# design.net
KiCad netlist of a schematic drawn in EasyEDA Pro
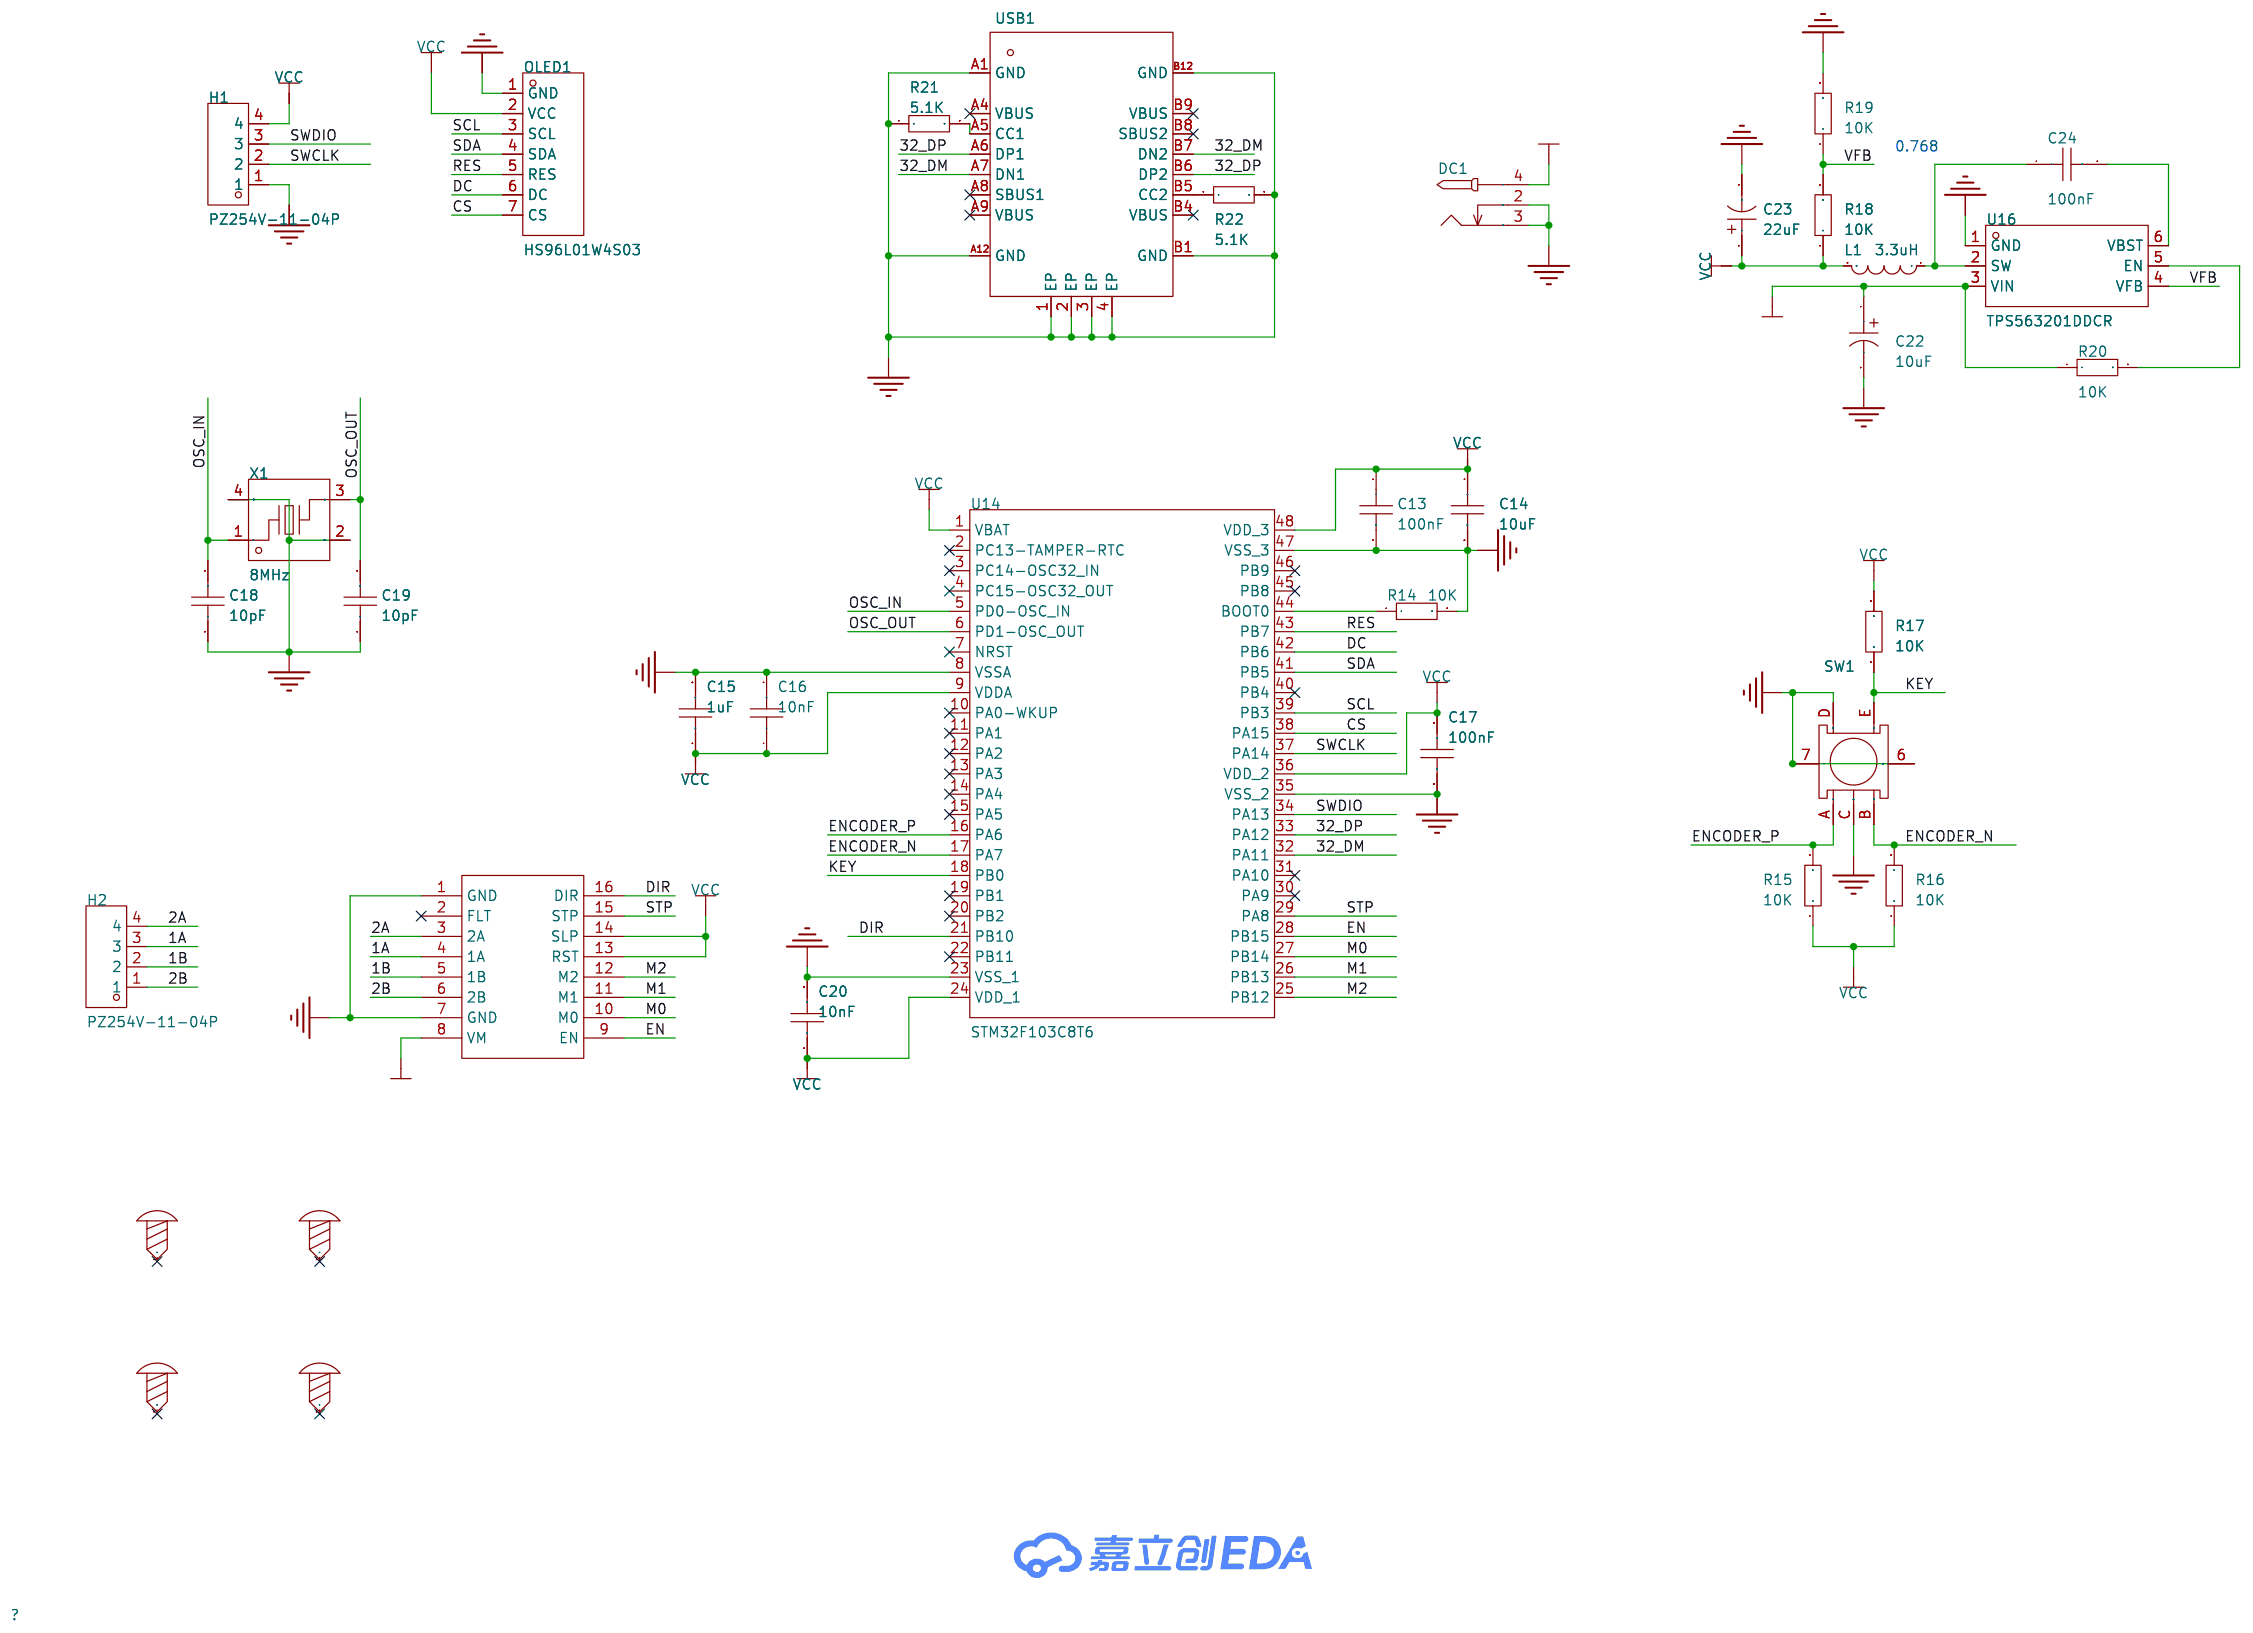
[diagram p0: schematic sheet]

(export (version "E")
  (design (tool "Eeschema 10.0.6"))
  (components
    (comp (ref "C13")
      (value "100nF")
      (footprint "easyedapro:C0603")
      (libsource (lib "easyedapro") (part "Capacitance"))
    )
    (comp (ref "C14")
      (value "10uF")
      (footprint "easyedapro:C0603")
      (libsource (lib "easyedapro") (part "Capacitance"))
    )
    (comp (ref "C15")
      (value "1uF")
      (footprint "easyedapro:C0603")
      (libsource (lib "easyedapro") (part "Capacitance"))
    )
    (comp (ref "C16")
      (value "10nF")
      (footprint "easyedapro:C0603")
      (libsource (lib "easyedapro") (part "Capacitance"))
    )
    (comp (ref "C17")
      (value "100nF")
      (footprint "easyedapro:C0603")
      (libsource (lib "easyedapro") (part "Capacitance"))
    )
    (comp (ref "C18")
      (value "10pF")
      (footprint "easyedapro:C0603")
      (libsource (lib "easyedapro") (part "Capacitance"))
    )
    (comp (ref "C19")
      (value "10pF")
      (footprint "easyedapro:C0603")
      (libsource (lib "easyedapro") (part "Capacitance"))
    )
    (comp (ref "C20")
      (value "10nF")
      (footprint "easyedapro:C0603")
      (libsource (lib "easyedapro") (part "Capacitance"))
    )
    (comp (ref "C22")
      (value "10uF")
      (footprint "easyedapro:CAP-TH_BD4.0-P1.50-D0.5-FD")
      (description "容值:10uF;精度:±20%;额定电压:16V;纹波电流:28mA@120Hz;等效串联电阻(ESR):-;")
      (fields
        (field (name "Manufacturer Part") "ECE-A1CKS100I")
        (field (name "Manufacturer") "PANASONIC(松下)")
      )
      (libsource (lib "easyedapro") (part "ECE-A1CKS100I"))
    )
    (comp (ref "C23")
      (value "22uF")
      (footprint "easyedapro:CAP-TH_BD5.0-P2.00-D0.5-FD-1")
      (description "容值:22uF;精度:±20%;额定电压:50V;")
      (fields (field (name "Manufacturer Part") "RGA220M1HBK-0511") (field (name "Manufacturer") "Lelon(立隆)"))
      (libsource (lib "easyedapro") (part "RGA220M1HBK-0511"))
    )
    (comp (ref "C24")
      (value "100nF")
      (footprint "easyedapro:C0603")
      (libsource (lib "easyedapro") (part "Capacitance"))
    )
    (comp (ref "DC1")
      (value "~")
      (footprint "easyedapro:DC-2.0")
      (libsource (lib "easyedapro") (part "DC电源接口"))
    )
    (comp (ref "H1")
      (value "PZ254V-11-04P")
      (footprint "easyedapro:HDR-TH_4P-P2.54-V-F")
      (fields (field (name "Manufacturer") "XFCN(兴飞)"))
      (libsource (lib "easyedapro") (part "2.54-1*4P母"))
    )
    (comp (ref "H2")
      (value "PZ254V-11-04P")
      (footprint "easyedapro:HDR-TH_4P-P2.54-V-F")
      (fields (field (name "Manufacturer") "XFCN(兴飞)"))
      (libsource (lib "easyedapro") (part "2.54-1*4P母"))
    )
    (comp (ref "L1")
      (value "3.3uH")
      (footprint "easyedapro:IND-SMD_L2.5-W2.0_AHP252010X")
      (description "电感值:3.3uH;精度:±20%;饱和电流(Isat):1.25A;")
      (fields (field (name "Manufacturer Part") "74404024033") (field (name "Manufacturer") "Wurth(伍尔特)"))
      (libsource (lib "easyedapro") (part "74404024033"))
    )
    (comp (ref "OLED1")
      (value "HS96L01W4S03")
      (footprint "easyedapro:OLED-TH_HS96L01W4S03")
      (fields (field (name "Manufacturer") "HS(汉昇)"))
      (libsource (lib "easyedapro") (part "HS96L01W4S03"))
    )
    (comp (ref "R14") (value "10K") (footprint "easyedapro:R0603") (libsource (lib "easyedapro") (part "电阻")))
    (comp (ref "R15") (value "10K") (footprint "easyedapro:R0603") (libsource (lib "easyedapro") (part "电阻")))
    (comp (ref "R16") (value "10K") (footprint "easyedapro:R0603") (libsource (lib "easyedapro") (part "电阻")))
    (comp (ref "R17") (value "10K") (footprint "easyedapro:R0603") (libsource (lib "easyedapro") (part "电阻")))
    (comp (ref "R18") (value "10K") (footprint "easyedapro:R0603") (libsource (lib "easyedapro") (part "电阻")))
    (comp (ref "R19") (value "10K") (footprint "easyedapro:R0603") (libsource (lib "easyedapro") (part "电阻")))
    (comp (ref "R20") (value "10K") (footprint "easyedapro:R0603") (libsource (lib "easyedapro") (part "电阻")))
    (comp (ref "R21")
      (value "5.1K")
      (footprint "easyedapro:R0603")
      (libsource (lib "easyedapro") (part "电阻"))
    )
    (comp (ref "R22")
      (value "5.1K")
      (footprint "easyedapro:R0603")
      (libsource (lib "easyedapro") (part "电阻"))
    )
    (comp (ref "SCREW1")
      (value "~")
      (footprint "easyedapro:M3螺丝")
      (libsource (lib "easyedapro") (part "螺丝孔"))
    )
    (comp (ref "SCREW2")
      (value "~")
      (footprint "easyedapro:M3螺丝")
      (libsource (lib "easyedapro") (part "螺丝孔"))
    )
    (comp (ref "SCREW3")
      (value "~")
      (footprint "easyedapro:M3螺丝")
      (libsource (lib "easyedapro") (part "螺丝孔"))
    )
    (comp (ref "SCREW4")
      (value "~")
      (footprint "easyedapro:M3螺丝")
      (libsource (lib "easyedapro") (part "螺丝孔"))
    )
    (comp (ref "SW1")
      (value "~")
      (footprint "easyedapro:旋转编码器")
      (libsource (lib "easyedapro") (part "旋转编码器"))
    )
    (comp (ref "U1")
      (value "~")
      (footprint "easyedapro:DRV8825模块")
      (libsource (lib "easyedapro") (part "DRV8825模块"))
    )
    (comp (ref "U14")
      (value "STM32F103C8T6")
      (footprint "easyedapro:LQFP-48_L7.0-W7.0-P0.50-LS9.0-BL")
      (fields (field (name "Manufacturer") "ST(意法半导体)"))
      (libsource (lib "easyedapro") (part "STM32F103C8T6"))
    )
    (comp (ref "U16")
      (value "TPS563201DDCR")
      (footprint "easyedapro:SOT-23-6_L2.9-W1.6-P0.95-LS2.8-BR")
      (description "功能类型:降压型;输出类型:可调;工作电压:4.5V~17V;输出电压:768mV~7V;输出电流:3A;")
      (fields (field (name "Manufacturer") "TI(德州仪器)"))
      (libsource (lib "easyedapro") (part "TPS563201DDCR"))
    )
    (comp (ref "USB1")
      (value "~")
      (footprint "easyedapro:USB_TYPE-C-16P")
      (libsource (lib "easyedapro") (part "USB_TYPE-C-16P"))
    )
    (comp (ref "X1")
      (value "8MHz")
      (footprint "easyedapro:CRYSTAL-SMD_4P-L3.2-W2.5-BL")
      (description "晶振类型:贴片晶振;频率:8MHz;常温频差:±10ppm;负载电容:20pF;频率稳定度:±20ppm;")
      (fields (field (name "Manufacturer Part") "X32258MSB4SI") (field (name "Manufacturer") "YXC(扬兴晶振)"))
      (libsource (lib "easyedapro") (part "X32258MSB4SI"))
    )
  )
  (nets
    (net (code "1") (name "/1A") (class "Default")
      (node (ref "H2") (pin "3") (pinfunction "3_3") (pintype "unspecified"))
      (node (ref "U1") (pin "4") (pinfunction "1A_4") (pintype "input"))
    )
    (net (code "2") (name "/1B") (class "Default")
      (node (ref "H2") (pin "2") (pinfunction "2_2") (pintype "unspecified"))
      (node (ref "U1") (pin "5") (pinfunction "1B_5") (pintype "input"))
    )
    (net (code "3") (name "/2A") (class "Default")
      (node (ref "H2") (pin "4") (pinfunction "4_4") (pintype "unspecified"))
      (node (ref "U1") (pin "3") (pinfunction "2A_3") (pintype "input"))
    )
    (net (code "4") (name "/2B") (class "Default")
      (node (ref "H2") (pin "1") (pinfunction "1_1") (pintype "unspecified"))
      (node (ref "U1") (pin "6") (pinfunction "2B_6") (pintype "input"))
    )
    (net (code "5") (name "/32_DM") (class "Default")
      (node (ref "U14") (pin "32") (pinfunction "PA11_32") (pintype "unspecified"))
      (node (ref "USB1") (pin "A7") (pinfunction "DN1_A7") (pintype "input"))
      (node (ref "USB1") (pin "B7") (pinfunction "DN2_B7") (pintype "input"))
    )
    (net (code "6") (name "/32_DP") (class "Default")
      (node (ref "U14") (pin "33") (pinfunction "PA12_33") (pintype "unspecified"))
      (node (ref "USB1") (pin "A6") (pinfunction "DP1_A6") (pintype "input"))
      (node (ref "USB1") (pin "B6") (pinfunction "DP2_B6") (pintype "input"))
    )
    (net (code "7") (name "/CS") (class "Default")
      (node (ref "OLED1") (pin "7") (pinfunction "CS_7") (pintype "unspecified"))
      (node (ref "U14") (pin "38") (pinfunction "PA15_38") (pintype "unspecified"))
    )
    (net (code "8") (name "/DC") (class "Default")
      (node (ref "OLED1") (pin "6") (pinfunction "DC_6") (pintype "unspecified"))
      (node (ref "U14") (pin "42") (pinfunction "PB6_42") (pintype "unspecified"))
    )
    (net (code "9") (name "/DIR") (class "Default")
      (node (ref "U1") (pin "16") (pinfunction "DIR_16") (pintype "input"))
      (node (ref "U14") (pin "21") (pinfunction "PB10_21") (pintype "unspecified"))
    )
    (net (code "10") (name "/EN") (class "Default")
      (node (ref "U1") (pin "9") (pinfunction "EN_9") (pintype "input"))
      (node (ref "U14") (pin "28") (pinfunction "PB15_28") (pintype "unspecified"))
    )
    (net (code "11") (name "/ENCODER_N") (class "Default")
      (node (ref "R16") (pin "2") (pinfunction "2_2") (pintype "input"))
      (node (ref "SW1") (pin "B") (pinfunction "B_B") (pintype "input"))
      (node (ref "U14") (pin "17") (pinfunction "PA7_17") (pintype "unspecified"))
    )
    (net (code "12") (name "/ENCODER_P") (class "Default")
      (node (ref "R15") (pin "2") (pinfunction "2_2") (pintype "input"))
      (node (ref "SW1") (pin "A") (pinfunction "A_A") (pintype "input"))
      (node (ref "U14") (pin "16") (pinfunction "PA6_16") (pintype "unspecified"))
    )
    (net (code "13") (name "/KEY") (class "Default")
      (node (ref "R17") (pin "1") (pinfunction "1_1") (pintype "input"))
      (node (ref "SW1") (pin "E") (pinfunction "E_E") (pintype "input"))
      (node (ref "U14") (pin "18") (pinfunction "PB0_18") (pintype "unspecified"))
    )
    (net (code "14") (name "/M0") (class "Default")
      (node (ref "U1") (pin "10") (pinfunction "M0_10") (pintype "input"))
      (node (ref "U14") (pin "27") (pinfunction "PB14_27") (pintype "unspecified"))
    )
    (net (code "15") (name "/M1") (class "Default")
      (node (ref "U1") (pin "11") (pinfunction "M1_11") (pintype "input"))
      (node (ref "U14") (pin "26") (pinfunction "PB13_26") (pintype "unspecified"))
    )
    (net (code "16") (name "/M2") (class "Default")
      (node (ref "U1") (pin "12") (pinfunction "M2_12") (pintype "input"))
      (node (ref "U14") (pin "25") (pinfunction "PB12_25") (pintype "unspecified"))
    )
    (net (code "17") (name "/OSC_IN") (class "Default")
      (node (ref "C18") (pin "2") (pinfunction "2_2") (pintype "input"))
      (node (ref "U14") (pin "5") (pinfunction "PD0-OSC_IN_5") (pintype "unspecified"))
      (node (ref "X1") (pin "1") (pinfunction "1_1") (pintype "input"))
    )
    (net (code "18") (name "/OSC_OUT") (class "Default")
      (node (ref "C19") (pin "2") (pinfunction "2_2") (pintype "input"))
      (node (ref "U14") (pin "6") (pinfunction "PD1-OSC_OUT_6") (pintype "unspecified"))
      (node (ref "X1") (pin "3") (pinfunction "3_3") (pintype "input"))
    )
    (net (code "19") (name "/RES") (class "Default")
      (node (ref "OLED1") (pin "5") (pinfunction "RES_5") (pintype "unspecified"))
      (node (ref "U14") (pin "43") (pinfunction "PB7_43") (pintype "unspecified"))
    )
    (net (code "20") (name "/SCL") (class "Default")
      (node (ref "OLED1") (pin "3") (pinfunction "SCL_3") (pintype "unspecified"))
      (node (ref "U14") (pin "39") (pinfunction "PB3_39") (pintype "unspecified"))
    )
    (net (code "21") (name "/SDA") (class "Default")
      (node (ref "OLED1") (pin "4") (pinfunction "SDA_4") (pintype "unspecified"))
      (node (ref "U14") (pin "41") (pinfunction "PB5_41") (pintype "unspecified"))
    )
    (net (code "22") (name "/STP") (class "Default")
      (node (ref "U1") (pin "15") (pinfunction "STP_15") (pintype "input"))
      (node (ref "U14") (pin "29") (pinfunction "PA8_29") (pintype "unspecified"))
    )
    (net (code "23") (name "/SWCLK") (class "Default")
      (node (ref "H1") (pin "2") (pinfunction "2_2") (pintype "unspecified"))
      (node (ref "U14") (pin "37") (pinfunction "PA14_37") (pintype "unspecified"))
    )
    (net (code "24") (name "/SWDIO") (class "Default")
      (node (ref "H1") (pin "3") (pinfunction "3_3") (pintype "unspecified"))
      (node (ref "U14") (pin "34") (pinfunction "PA13_34") (pintype "unspecified"))
    )
    (net (code "25") (name "/VFB") (class "Default")
      (node (ref "R18") (pin "2") (pinfunction "2_2") (pintype "input"))
      (node (ref "R19") (pin "1") (pinfunction "1_1") (pintype "input"))
      (node (ref "U16") (pin "4") (pinfunction "VFB_4") (pintype "unspecified"))
    )
    (net (code "26") (name "12V") (class "Default")
      (node (ref "C22") (pin "1") (pinfunction "1_1") (pintype "input"))
      (node (ref "DC1") (pin "4") (pinfunction "4_4") (pintype "input"))
      (node (ref "R20") (pin "1") (pinfunction "1_1") (pintype "input"))
      (node (ref "U1") (pin "8") (pinfunction "VM_8") (pintype "input"))
      (node (ref "U16") (pin "3") (pinfunction "VIN_3") (pintype "unspecified"))
    )
    (net (code "27") (name "GND") (class "Default")
      (node (ref "C13") (pin "2") (pinfunction "2_2") (pintype "input"))
      (node (ref "C14") (pin "2") (pinfunction "2_2") (pintype "input"))
      (node (ref "C15") (pin "2") (pinfunction "2_2") (pintype "input"))
      (node (ref "C16") (pin "2") (pinfunction "2_2") (pintype "input"))
      (node (ref "C17") (pin "2") (pinfunction "2_2") (pintype "input"))
      (node (ref "C18") (pin "1") (pinfunction "1_1") (pintype "input"))
      (node (ref "C19") (pin "1") (pinfunction "1_1") (pintype "input"))
      (node (ref "C20") (pin "2") (pinfunction "2_2") (pintype "input"))
      (node (ref "C22") (pin "2") (pinfunction "2_2") (pintype "input"))
      (node (ref "C23") (pin "2") (pinfunction "2_2") (pintype "input"))
      (node (ref "DC1") (pin "2") (pinfunction "2_2") (pintype "input"))
      (node (ref "DC1") (pin "3") (pinfunction "3_3") (pintype "input"))
      (node (ref "H1") (pin "1") (pinfunction "1_1") (pintype "unspecified"))
      (node (ref "OLED1") (pin "1") (pinfunction "GND_1") (pintype "unspecified"))
      (node (ref "R14") (pin "2") (pinfunction "2_2") (pintype "input"))
      (node (ref "R19") (pin "2") (pinfunction "2_2") (pintype "input"))
      (node (ref "R21") (pin "1") (pinfunction "1_1") (pintype "input"))
      (node (ref "R22") (pin "2") (pinfunction "2_2") (pintype "input"))
      (node (ref "SW1") (pin "6") (pinfunction "6_6") (pintype "input"))
      (node (ref "SW1") (pin "7") (pinfunction "7_7") (pintype "input"))
      (node (ref "SW1") (pin "C") (pinfunction "C_C") (pintype "input"))
      (node (ref "SW1") (pin "D") (pinfunction "D_D") (pintype "input"))
      (node (ref "U1") (pin "1") (pinfunction "GND_1") (pintype "input"))
      (node (ref "U1") (pin "7") (pinfunction "GND_7") (pintype "input"))
      (node (ref "U14") (pin "23") (pinfunction "VSS_1_23") (pintype "unspecified"))
      (node (ref "U14") (pin "35") (pinfunction "VSS_2_35") (pintype "unspecified"))
      (node (ref "U14") (pin "47") (pinfunction "VSS_3_47") (pintype "unspecified"))
      (node (ref "U14") (pin "8") (pinfunction "VSSA_8") (pintype "unspecified"))
      (node (ref "U16") (pin "1") (pinfunction "GND_1") (pintype "unspecified"))
      (node (ref "USB1") (pin "1") (pinfunction "EP_1") (pintype "input"))
      (node (ref "USB1") (pin "2") (pinfunction "EP_2") (pintype "input"))
      (node (ref "USB1") (pin "3") (pinfunction "EP_3") (pintype "input"))
      (node (ref "USB1") (pin "4") (pinfunction "EP_4") (pintype "input"))
      (node (ref "USB1") (pin "A1") (pinfunction "GND_A1") (pintype "input"))
      (node (ref "USB1") (pin "A12") (pinfunction "GND_A12") (pintype "input"))
      (node (ref "USB1") (pin "B1") (pinfunction "GND_B1") (pintype "input"))
      (node (ref "USB1") (pin "B12") (pinfunction "GND_B12") (pintype "input"))
      (node (ref "X1") (pin "2") (pinfunction "GND_2") (pintype "input"))
      (node (ref "X1") (pin "4") (pinfunction "GND_4") (pintype "input"))
    )
    (net (code "28") (name "Net-(U14-BOOT0)") (class "Default")
      (node (ref "R14") (pin "1") (pinfunction "1_1") (pintype "input"))
      (node (ref "U14") (pin "44") (pinfunction "BOOT0_44") (pintype "unspecified"))
    )
    (net (code "29") (name "Net-(U16-EN)") (class "Default")
      (node (ref "R20") (pin "2") (pinfunction "2_2") (pintype "input"))
      (node (ref "U16") (pin "5") (pinfunction "EN_5") (pintype "unspecified"))
    )
    (net (code "30") (name "Net-(U16-SW)") (class "Default")
      (node (ref "C24") (pin "1") (pinfunction "1_1") (pintype "input"))
      (node (ref "L1") (pin "1") (pinfunction "1_1") (pintype "unspecified"))
      (node (ref "U16") (pin "2") (pinfunction "SW_2") (pintype "unspecified"))
    )
    (net (code "31") (name "Net-(U16-VBST)") (class "Default")
      (node (ref "C24") (pin "2") (pinfunction "2_2") (pintype "input"))
      (node (ref "U16") (pin "6") (pinfunction "VBST_6") (pintype "unspecified"))
    )
    (net (code "32") (name "Net-(USB1-CC1)") (class "Default")
      (node (ref "R21") (pin "2") (pinfunction "2_2") (pintype "input"))
      (node (ref "USB1") (pin "A5") (pinfunction "CC1_A5") (pintype "input"))
    )
    (net (code "33") (name "Net-(USB1-CC2)") (class "Default")
      (node (ref "R22") (pin "1") (pinfunction "1_1") (pintype "input"))
      (node (ref "USB1") (pin "B5") (pinfunction "CC2_B5") (pintype "input"))
    )
    (net (code "34") (name "VCC") (class "Default")
      (node (ref "C13") (pin "1") (pinfunction "1_1") (pintype "input"))
      (node (ref "C14") (pin "1") (pinfunction "1_1") (pintype "input"))
      (node (ref "C15") (pin "1") (pinfunction "1_1") (pintype "input"))
      (node (ref "C16") (pin "1") (pinfunction "1_1") (pintype "input"))
      (node (ref "C17") (pin "1") (pinfunction "1_1") (pintype "input"))
      (node (ref "C20") (pin "1") (pinfunction "1_1") (pintype "input"))
      (node (ref "C23") (pin "1") (pinfunction "1_1") (pintype "input"))
      (node (ref "H1") (pin "4") (pinfunction "4_4") (pintype "unspecified"))
      (node (ref "L1") (pin "2") (pinfunction "2_2") (pintype "unspecified"))
      (node (ref "OLED1") (pin "2") (pinfunction "VCC_2") (pintype "unspecified"))
      (node (ref "R15") (pin "1") (pinfunction "1_1") (pintype "input"))
      (node (ref "R16") (pin "1") (pinfunction "1_1") (pintype "input"))
      (node (ref "R17") (pin "2") (pinfunction "2_2") (pintype "input"))
      (node (ref "R18") (pin "1") (pinfunction "1_1") (pintype "input"))
      (node (ref "U1") (pin "13") (pinfunction "RST_13") (pintype "input"))
      (node (ref "U1") (pin "14") (pinfunction "SLP_14") (pintype "input"))
      (node (ref "U14") (pin "1") (pinfunction "VBAT_1") (pintype "unspecified"))
      (node (ref "U14") (pin "24") (pinfunction "VDD_1_24") (pintype "unspecified"))
      (node (ref "U14") (pin "36") (pinfunction "VDD_2_36") (pintype "unspecified"))
      (node (ref "U14") (pin "48") (pinfunction "VDD_3_48") (pintype "unspecified"))
      (node (ref "U14") (pin "9") (pinfunction "VDDA_9") (pintype "unspecified"))
    )
    (net (code "35") (name "unconnected-(SCREW1-Pad1)") (class "Default")
      (node (ref "SCREW1") (pin "1") (pinfunction "1_1") (pintype "input+no_connect"))
    )
    (net (code "36") (name "unconnected-(SCREW2-Pad1)") (class "Default")
      (node (ref "SCREW2") (pin "1") (pinfunction "1_1") (pintype "input+no_connect"))
    )
    (net (code "37") (name "unconnected-(SCREW3-Pad1)") (class "Default")
      (node (ref "SCREW3") (pin "1") (pinfunction "1_1") (pintype "input+no_connect"))
    )
    (net (code "38") (name "unconnected-(SCREW4-Pad1)") (class "Default")
      (node (ref "SCREW4") (pin "1") (pinfunction "1_1") (pintype "input+no_connect"))
    )
    (net (code "39") (name "unconnected-(U1-FLT-Pad2)") (class "Default")
      (node (ref "U1") (pin "2") (pinfunction "FLT_2") (pintype "input+no_connect"))
    )
    (net (code "40") (name "unconnected-(U14-NRST-Pad7)") (class "Default")
      (node (ref "U14") (pin "7") (pinfunction "NRST_7") (pintype "unspecified+no_connect"))
    )
    (net (code "41") (name "unconnected-(U14-PA0-WKUP-Pad10)") (class "Default")
      (node (ref "U14") (pin "10") (pinfunction "PA0-WKUP_10") (pintype "unspecified+no_connect"))
    )
    (net (code "42") (name "unconnected-(U14-PA1-Pad11)") (class "Default")
      (node (ref "U14") (pin "11") (pinfunction "PA1_11") (pintype "unspecified+no_connect"))
    )
    (net (code "43") (name "unconnected-(U14-PA2-Pad12)") (class "Default")
      (node (ref "U14") (pin "12") (pinfunction "PA2_12") (pintype "unspecified+no_connect"))
    )
    (net (code "44") (name "unconnected-(U14-PA3-Pad13)") (class "Default")
      (node (ref "U14") (pin "13") (pinfunction "PA3_13") (pintype "unspecified+no_connect"))
    )
    (net (code "45") (name "unconnected-(U14-PA4-Pad14)") (class "Default")
      (node (ref "U14") (pin "14") (pinfunction "PA4_14") (pintype "unspecified+no_connect"))
    )
    (net (code "46") (name "unconnected-(U14-PA5-Pad15)") (class "Default")
      (node (ref "U14") (pin "15") (pinfunction "PA5_15") (pintype "unspecified+no_connect"))
    )
    (net (code "47") (name "unconnected-(U14-PA9-Pad30)") (class "Default")
      (node (ref "U14") (pin "30") (pinfunction "PA9_30") (pintype "unspecified+no_connect"))
    )
    (net (code "48") (name "unconnected-(U14-PA10-Pad31)") (class "Default")
      (node (ref "U14") (pin "31") (pinfunction "PA10_31") (pintype "unspecified+no_connect"))
    )
    (net (code "49") (name "unconnected-(U14-PB1-Pad19)") (class "Default")
      (node (ref "U14") (pin "19") (pinfunction "PB1_19") (pintype "unspecified+no_connect"))
    )
    (net (code "50") (name "unconnected-(U14-PB2-Pad20)") (class "Default")
      (node (ref "U14") (pin "20") (pinfunction "PB2_20") (pintype "unspecified+no_connect"))
    )
    (net (code "51") (name "unconnected-(U14-PB4-Pad40)") (class "Default")
      (node (ref "U14") (pin "40") (pinfunction "PB4_40") (pintype "unspecified+no_connect"))
    )
    (net (code "52") (name "unconnected-(U14-PB8-Pad45)") (class "Default")
      (node (ref "U14") (pin "45") (pinfunction "PB8_45") (pintype "unspecified+no_connect"))
    )
    (net (code "53") (name "unconnected-(U14-PB9-Pad46)") (class "Default")
      (node (ref "U14") (pin "46") (pinfunction "PB9_46") (pintype "unspecified+no_connect"))
    )
    (net (code "54") (name "unconnected-(U14-PB11-Pad22)") (class "Default")
      (node (ref "U14") (pin "22") (pinfunction "PB11_22") (pintype "unspecified+no_connect"))
    )
    (net (code "55") (name "unconnected-(U14-PC13-TAMPER-RTC-Pad2)") (class "Default")
      (node (ref "U14") (pin "2") (pinfunction "PC13-TAMPER-RTC_2") (pintype "unspecified+no_connect"))
    )
    (net (code "56") (name "unconnected-(U14-PC14-OSC32_IN-Pad3)") (class "Default")
      (node (ref "U14") (pin "3") (pinfunction "PC14-OSC32_IN_3") (pintype "unspecified+no_connect"))
    )
    (net (code "57") (name "unconnected-(U14-PC15-OSC32_OUT-Pad4)") (class "Default")
      (node (ref "U14") (pin "4") (pinfunction "PC15-OSC32_OUT_4") (pintype "unspecified+no_connect"))
    )
    (net (code "58") (name "unconnected-(USB1-SBUS1-PadA8)") (class "Default")
      (node (ref "USB1") (pin "A8") (pinfunction "SBUS1_A8") (pintype "input+no_connect"))
    )
    (net (code "59") (name "unconnected-(USB1-SBUS2-PadB8)") (class "Default")
      (node (ref "USB1") (pin "B8") (pinfunction "SBUS2_B8") (pintype "input+no_connect"))
    )
    (net (code "60") (name "unconnected-(USB1-VBUS-PadA4)") (class "Default")
      (node (ref "USB1") (pin "A4") (pinfunction "VBUS_A4") (pintype "input+no_connect"))
    )
    (net (code "61") (name "unconnected-(USB1-VBUS-PadA9)") (class "Default")
      (node (ref "USB1") (pin "A9") (pinfunction "VBUS_A9") (pintype "input+no_connect"))
    )
    (net (code "62") (name "unconnected-(USB1-VBUS-PadB4)") (class "Default")
      (node (ref "USB1") (pin "B4") (pinfunction "VBUS_B4") (pintype "input+no_connect"))
    )
    (net (code "63") (name "unconnected-(USB1-VBUS-PadB9)") (class "Default")
      (node (ref "USB1") (pin "B9") (pinfunction "VBUS_B9") (pintype "input+no_connect"))
    )
  )
)
